# SENSOR_BOARD.net
KiCad netlist of a schematic drawn in EAGLE
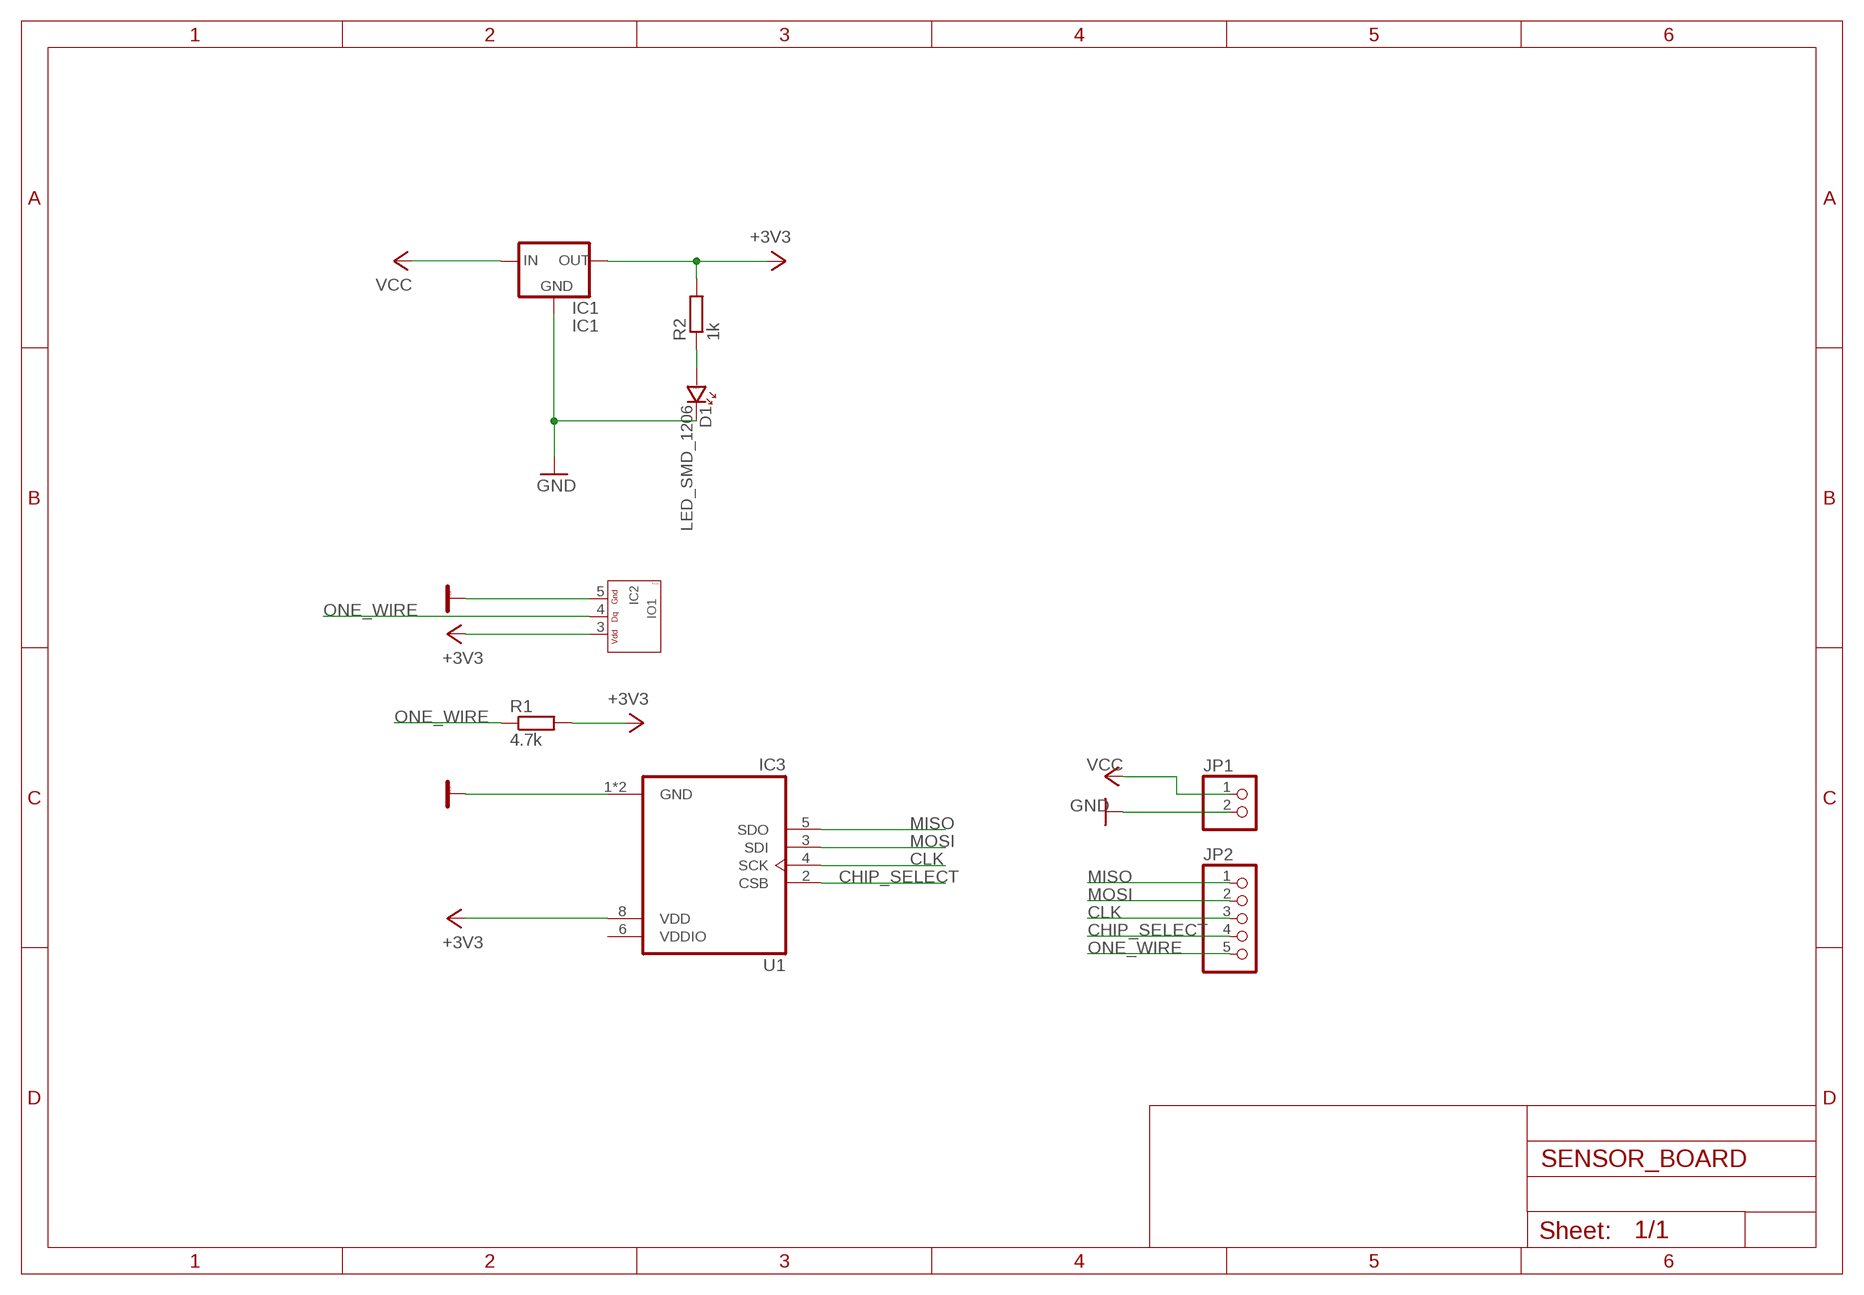
[diagram p0: schematic, sheet 1]

(export (version "E")
  (design (tool "Eeschema 10.0.6"))
  (components
    (comp (ref "D1")
      (value "LED_SMD_1206")
      (footprint "eagle-import:P1206")
      (libsource (lib "eagle-import") (part "LED_SMD_1206"))
    )
    (comp (ref "IC1")
      (value "IC1")
      (footprint "eagle-import:SOT223")
      (fields (field (name "MF") "Texas Instruments") (field (name "MPN") "LM1117MP-3.3"))
      (libsource (lib "eagle-import") (part "LM1117?-MP3.3"))
    )
    (comp (ref "IO1")
      (value "IC2")
      (footprint "eagle-import:SO08")
      (libsource (lib "eagle-import") (part "DS18B20_SO8"))
    )
    (comp (ref "JP1")
      (value "PINHD-1X2")
      (footprint "eagle-import:1X02")
      (libsource (lib "eagle-import") (part "PINHD-1X2"))
    )
    (comp (ref "JP2")
      (value "PINHD-1X5")
      (footprint "eagle-import:1X05")
      (libsource (lib "eagle-import") (part "PINHD-1X5"))
    )
    (comp (ref "R1")
      (value "4.7k")
      (footprint "eagle-import:R0603")
      (libsource (lib "eagle-import") (part "R-EU_R0603"))
    )
    (comp (ref "R2")
      (value "1k")
      (footprint "eagle-import:R0603")
      (libsource (lib "eagle-import") (part "R-EU_R0603"))
    )
    (comp (ref "U1")
      (value "IC3")
      (footprint "eagle-import:PSON65P250X250X100-8N")
      (fields (field (name "MF") "Bosch") (field (name "MP") "BME280"))
      (libsource (lib "eagle-import") (part "BME280"))
    )
  )
  (nets
    (net (code "1") (name "+3V3") (class "Default")
      (node (ref "IC1") (pin "2") (pinfunction "OUT_2") (pintype "passive"))
      (node (ref "IC1") (pin "4") (pinfunction "OUT_4") (pintype "passive"))
      (node (ref "IO1") (pin "3") (pinfunction "+VCC_3") (pintype "power_in"))
      (node (ref "R1") (pin "2") (pinfunction "2_2") (pintype "passive"))
      (node (ref "R2") (pin "2") (pinfunction "2_2") (pintype "passive"))
      (node (ref "U1") (pin "8") (pinfunction "VDD_8") (pintype "power_in"))
    )
    (net (code "2") (name "/CHIP_SELECT") (class "Default")
      (node (ref "JP2") (pin "4") (pinfunction "4_4") (pintype "passive"))
      (node (ref "U1") (pin "2") (pinfunction "CSB_2") (pintype "input"))
    )
    (net (code "3") (name "/CLK") (class "Default")
      (node (ref "JP2") (pin "3") (pinfunction "3_3") (pintype "passive"))
      (node (ref "U1") (pin "4") (pinfunction "SCK_4") (pintype "input"))
    )
    (net (code "4") (name "/MISO") (class "Default")
      (node (ref "JP2") (pin "1") (pinfunction "1_1") (pintype "passive"))
      (node (ref "U1") (pin "5") (pinfunction "SDO_5") (pintype "bidirectional"))
    )
    (net (code "5") (name "/MOSI") (class "Default")
      (node (ref "JP2") (pin "2") (pinfunction "2_2") (pintype "passive"))
      (node (ref "U1") (pin "3") (pinfunction "SDI_3") (pintype "bidirectional"))
    )
    (net (code "6") (name "/ONE_WIRE") (class "Default")
      (node (ref "IO1") (pin "4") (pinfunction "1WIRE_4") (pintype "bidirectional"))
      (node (ref "JP2") (pin "5") (pinfunction "5_5") (pintype "passive"))
      (node (ref "R1") (pin "1") (pinfunction "1_1") (pintype "passive"))
    )
    (net (code "7") (name "/VDDIO") (class "Default")
      (node (ref "U1") (pin "6") (pinfunction "VDDIO_6") (pintype "power_in"))
    )
    (net (code "8") (name "GND") (class "Default")
      (node (ref "D1") (pin "K") (pinfunction "K_K") (pintype "passive"))
      (node (ref "IC1") (pin "1") (pinfunction "GND_1") (pintype "input"))
      (node (ref "IO1") (pin "5") (pinfunction "GND_5") (pintype "power_in"))
      (node (ref "JP1") (pin "2") (pinfunction "2_2") (pintype "passive"))
      (node (ref "U1") (pin "1") (pinfunction "GND_1") (pintype "power_in"))
      (node (ref "U1") (pin "7") (pinfunction "GND_7") (pintype "power_in"))
    )
    (net (code "9") (name "Net-(D1-PadA)") (class "Default")
      (node (ref "D1") (pin "A") (pinfunction "A_A") (pintype "passive"))
      (node (ref "R2") (pin "1") (pinfunction "1_1") (pintype "passive"))
    )
    (net (code "10") (name "VCC") (class "Default")
      (node (ref "IC1") (pin "3") (pinfunction "IN_3") (pintype "input"))
      (node (ref "JP1") (pin "1") (pinfunction "1_1") (pintype "passive"))
    )
  )
)
